# 07-AUDIO_MAIN.net
KiCad netlist of a schematic drawn in Altium Designer
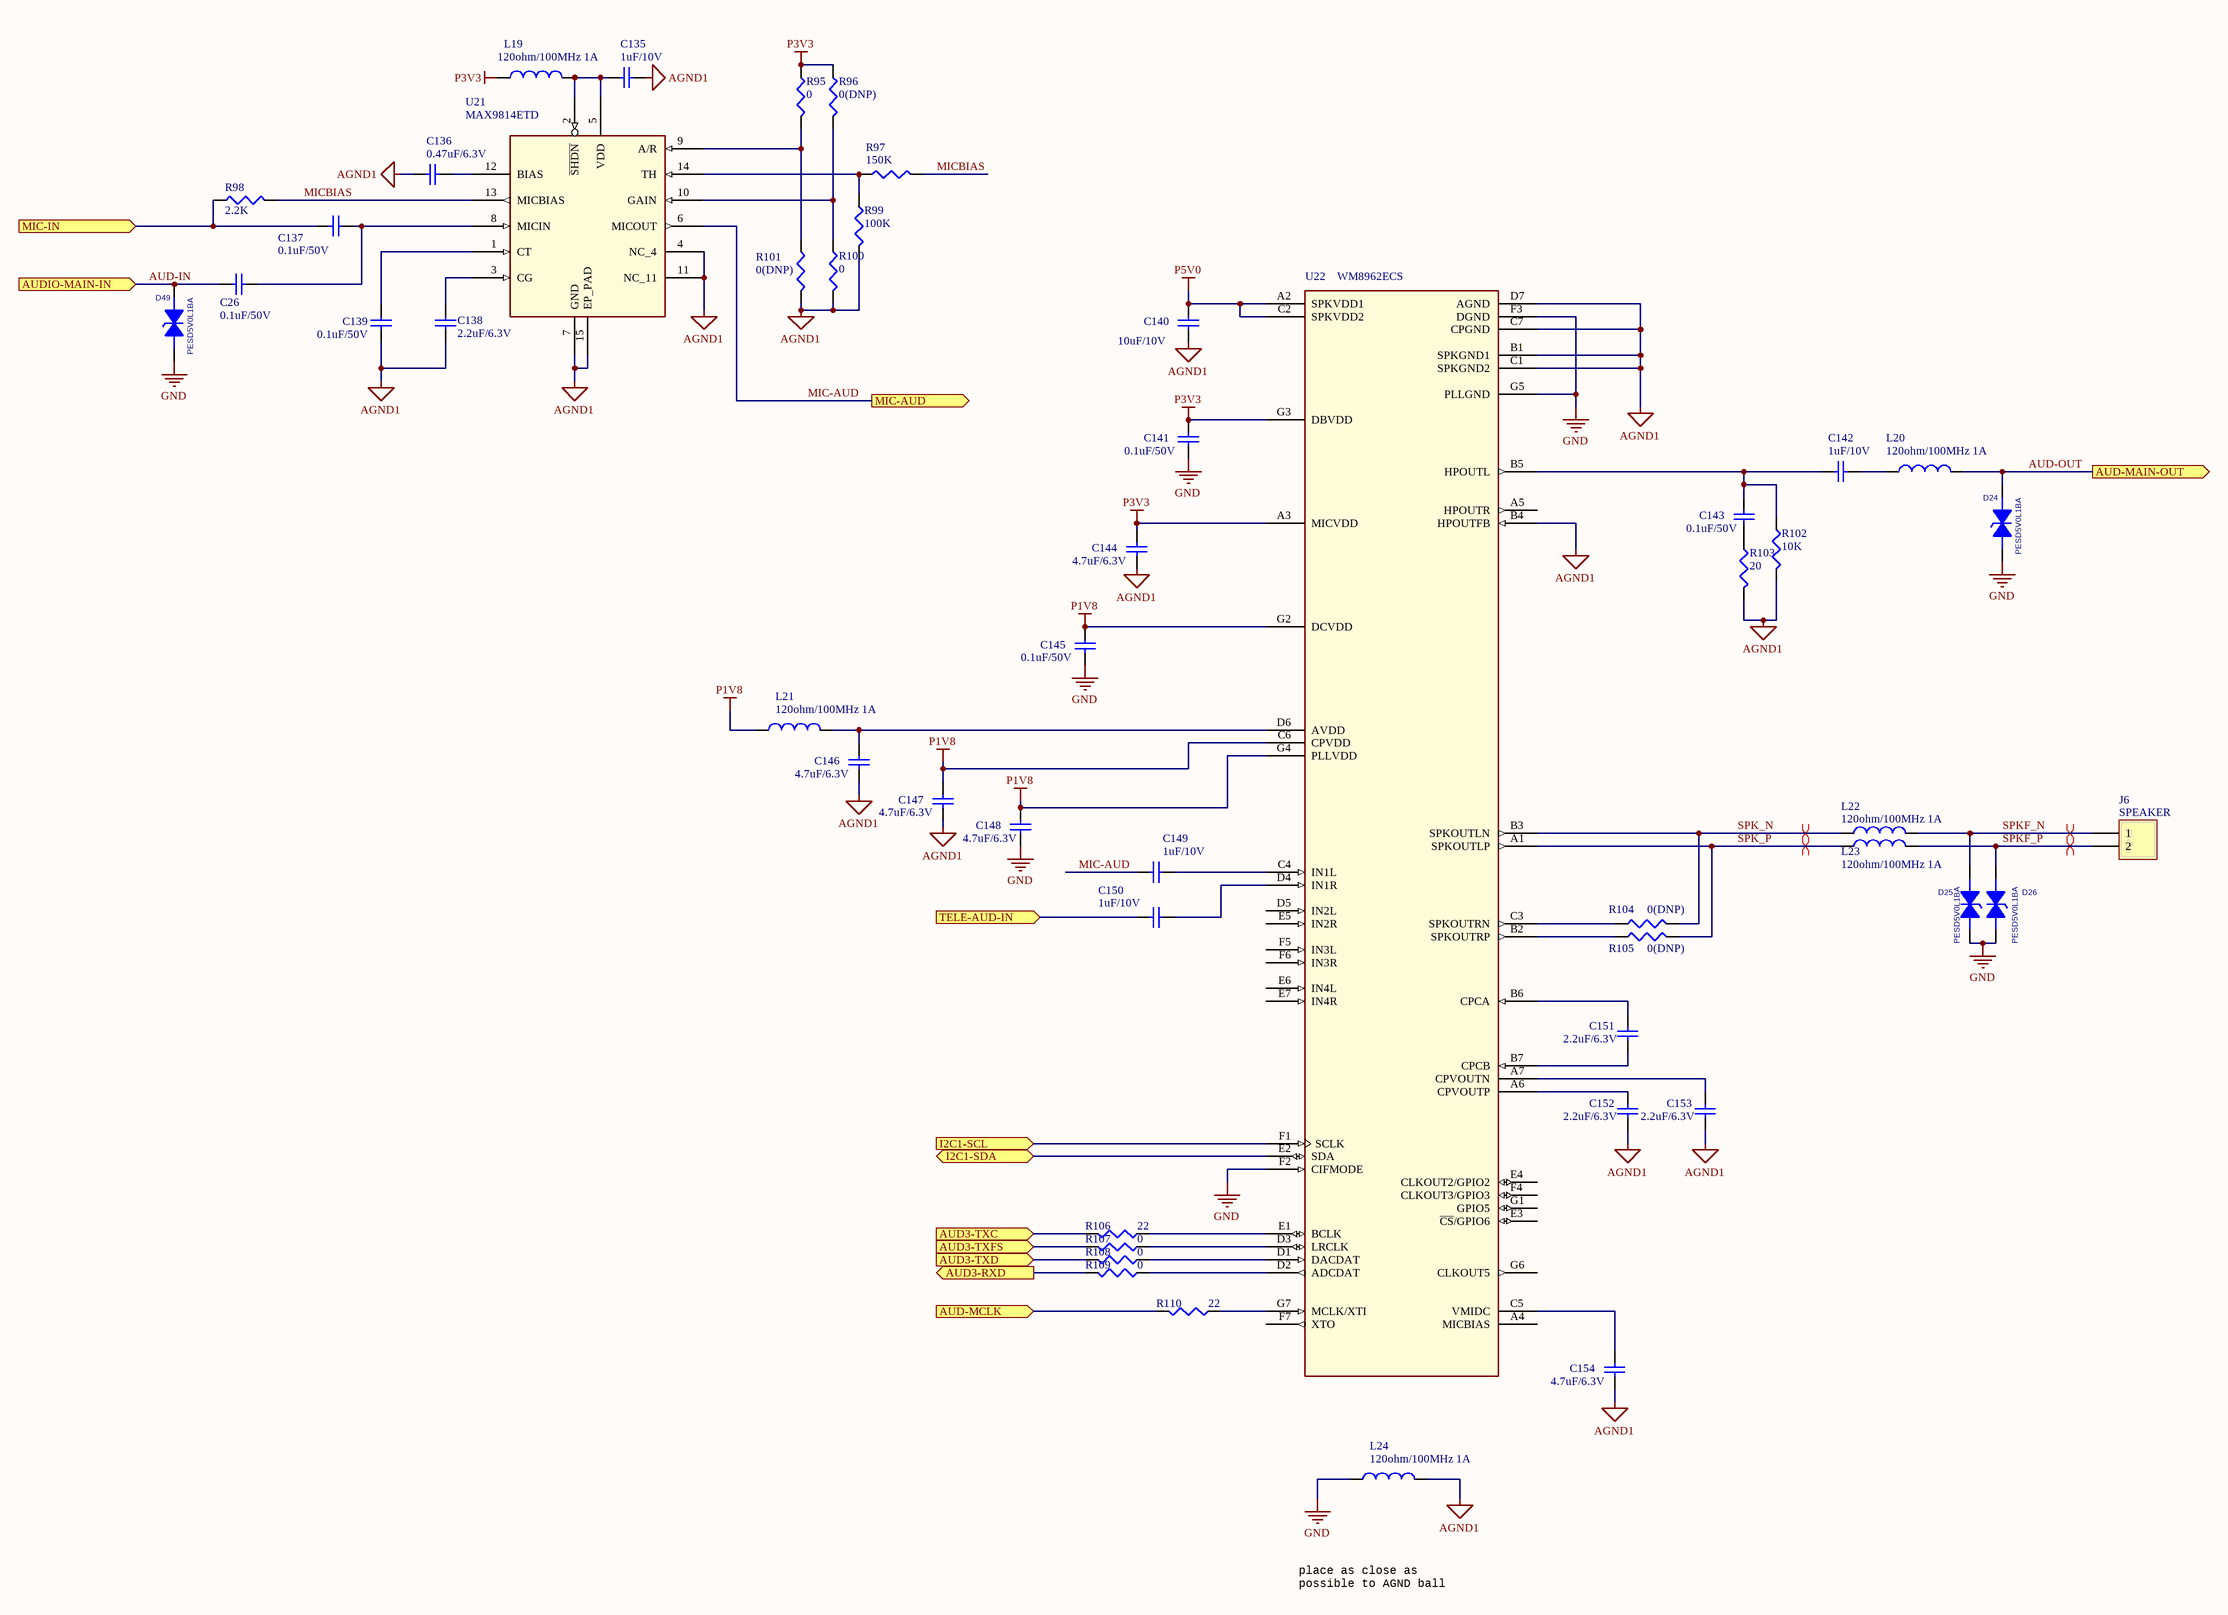
[diagram p0: 07-AUDIO_MAIN.SchDoc]

(export (version "E")
  (design (tool "Eeschema 10.0.6"))
  (components
    (comp (ref "C26")
      (value "0.1uF/50V")
      (footprint "0402")
      (description "Capacitor")
      (fields (field (name "PUBLISHER") "Altium Limited"))
      (libsource (lib "Miscellaneous Devices") (part "Cap"))
    )
    (comp (ref "C135")
      (value "1uF/10V")
      (footprint "0402")
      (description "Capacitor")
      (fields (field (name "PUBLISHER") "Altium Limited"))
      (libsource (lib "Miscellaneous Devices") (part "Cap"))
    )
    (comp (ref "C136")
      (value "0.47uF/6.3V")
      (footprint "0402")
      (description "Capacitor")
      (fields (field (name "PUBLISHER") "Altium Limited"))
      (libsource (lib "Miscellaneous Devices") (part "Cap"))
    )
    (comp (ref "C137")
      (value "0.1uF/50V")
      (footprint "0402")
      (description "Capacitor")
      (fields (field (name "PUBLISHER") "Altium Limited"))
      (libsource (lib "Miscellaneous Devices") (part "Cap"))
    )
    (comp (ref "C138")
      (value "2.2uF/6.3V")
      (footprint "0402")
      (description "Capacitor")
      (fields (field (name "PUBLISHER") "Altium Limited"))
      (libsource (lib "Miscellaneous Devices") (part "Cap"))
    )
    (comp (ref "C139")
      (value "0.1uF/50V")
      (footprint "0402")
      (description "Capacitor")
      (fields (field (name "PUBLISHER") "Altium Limited"))
      (libsource (lib "Miscellaneous Devices") (part "Cap"))
    )
    (comp (ref "C140")
      (value "10uF/10V")
      (footprint "0805")
      (description "Capacitor")
      (fields (field (name "PUBLISHER") "Altium Limited"))
      (libsource (lib "Miscellaneous Devices") (part "Cap"))
    )
    (comp (ref "C141")
      (value "0.1uF/50V")
      (footprint "0402")
      (description "Capacitor")
      (fields (field (name "PUBLISHER") "Altium Limited"))
      (libsource (lib "Miscellaneous Devices") (part "Cap"))
    )
    (comp (ref "C142")
      (value "1uF/10V")
      (footprint "0402")
      (description "Capacitor")
      (fields (field (name "PUBLISHER") "Altium Limited"))
      (libsource (lib "Miscellaneous Devices") (part "Cap"))
    )
    (comp (ref "C143")
      (value "0.1uF/50V")
      (footprint "0402")
      (description "Capacitor")
      (fields (field (name "PUBLISHER") "Altium Limited"))
      (libsource (lib "Miscellaneous Devices") (part "Cap"))
    )
    (comp (ref "C144")
      (value "4.7uF/6.3V")
      (footprint "0603")
      (description "Capacitor")
      (fields (field (name "PUBLISHER") "Altium Limited"))
      (libsource (lib "Miscellaneous Devices") (part "Cap"))
    )
    (comp (ref "C145")
      (value "0.1uF/50V")
      (footprint "0402")
      (description "Capacitor")
      (fields (field (name "PUBLISHER") "Altium Limited"))
      (libsource (lib "Miscellaneous Devices") (part "Cap"))
    )
    (comp (ref "C146")
      (value "4.7uF/6.3V")
      (footprint "0603")
      (description "Capacitor")
      (fields (field (name "PUBLISHER") "Altium Limited"))
      (libsource (lib "Miscellaneous Devices") (part "Cap"))
    )
    (comp (ref "C147")
      (value "4.7uF/6.3V")
      (footprint "0603")
      (description "Capacitor")
      (fields (field (name "PUBLISHER") "Altium Limited"))
      (libsource (lib "Miscellaneous Devices") (part "Cap"))
    )
    (comp (ref "C148")
      (value "4.7uF/6.3V")
      (footprint "0603")
      (description "Capacitor")
      (fields (field (name "PUBLISHER") "Altium Limited"))
      (libsource (lib "Miscellaneous Devices") (part "Cap"))
    )
    (comp (ref "C149")
      (value "1uF/10V")
      (footprint "0402")
      (description "Capacitor")
      (fields (field (name "PUBLISHER") "Altium Limited"))
      (libsource (lib "Miscellaneous Devices") (part "Cap"))
    )
    (comp (ref "C150")
      (value "1uF/10V")
      (footprint "0402")
      (description "Capacitor")
      (fields (field (name "PUBLISHER") "Altium Limited"))
      (libsource (lib "Miscellaneous Devices") (part "Cap"))
    )
    (comp (ref "C151")
      (value "2.2uF/6.3V")
      (footprint "0402")
      (description "Capacitor")
      (fields (field (name "PUBLISHER") "Altium Limited"))
      (libsource (lib "Miscellaneous Devices") (part "Cap"))
    )
    (comp (ref "C152")
      (value "2.2uF/6.3V")
      (footprint "0402")
      (description "Capacitor")
      (fields (field (name "PUBLISHER") "Altium Limited"))
      (libsource (lib "Miscellaneous Devices") (part "Cap"))
    )
    (comp (ref "C153")
      (value "2.2uF/6.3V")
      (footprint "0402")
      (description "Capacitor")
      (fields (field (name "PUBLISHER") "Altium Limited"))
      (libsource (lib "Miscellaneous Devices") (part "Cap"))
    )
    (comp (ref "C154")
      (value "4.7uF/6.3V")
      (footprint "0603")
      (description "Capacitor")
      (fields (field (name "PUBLISHER") "Altium Limited"))
      (libsource (lib "Miscellaneous Devices") (part "Cap"))
    )
    (comp (ref "D24") (value "PESD5V0L1BA") (libsource (lib "*") (part "PESD")))
    (comp (ref "D25") (value "PESD5V0L1BA") (libsource (lib "*") (part "PESD")))
    (comp (ref "D26") (value "PESD5V0L1BA") (libsource (lib "*") (part "PESD")))
    (comp (ref "D49") (value "PESD5V0L1BA") (libsource (lib "*") (part "PESD")))
    (comp (ref "J6")
      (value "SPEAKER")
      (footprint "1250WV-S-2P")
      (description "Header, 2-Pin")
      (fields (field (name "PUBLISHER") "Altium Limited"))
      (libsource (lib "Miscellaneous Connectors") (part "Header 2"))
    )
    (comp (ref "L19")
      (value "120ohm/100MHz 1A")
      (footprint "0603")
      (description "Inductor")
      (fields (field (name "PUBLISHER") "Altium Limited"))
      (libsource (lib "") (part "Inductor_1"))
    )
    (comp (ref "L20")
      (value "120ohm/100MHz 1A")
      (footprint "0603")
      (description "Inductor")
      (fields (field (name "PUBLISHER") "Altium Limited"))
      (libsource (lib "") (part "Inductor_1"))
    )
    (comp (ref "L21")
      (value "120ohm/100MHz 1A")
      (footprint "0603")
      (description "Inductor")
      (fields (field (name "PUBLISHER") "Altium Limited"))
      (libsource (lib "") (part "Inductor_1"))
    )
    (comp (ref "L22")
      (value "120ohm/100MHz 1A")
      (footprint "0603")
      (description "Inductor")
      (fields (field (name "PUBLISHER") "Altium Limited"))
      (libsource (lib "Miscellaneous Devices") (part "Inductor"))
    )
    (comp (ref "L23")
      (value "120ohm/100MHz 1A")
      (footprint "0603")
      (description "Inductor")
      (fields (field (name "PUBLISHER") "Altium Limited"))
      (libsource (lib "Miscellaneous Devices") (part "Inductor"))
    )
    (comp (ref "L24")
      (value "120ohm/100MHz 1A")
      (footprint "0603")
      (description "Inductor")
      (fields (field (name "PUBLISHER") "Altium Limited"))
      (libsource (lib "") (part "Inductor_1"))
    )
    (comp (ref "R95") (value "0") (footprint "0402") (libsource (lib "*") (part "CR16-1003FM")))
    (comp (ref "R96") (value "0(DNP)") (footprint "0402") (libsource (lib "*") (part "CR16-1003FM")))
    (comp (ref "R97") (value "150K") (footprint "0402") (libsource (lib "*") (part "CR16-1003FM")))
    (comp (ref "R98") (value "2.2K") (footprint "0402") (libsource (lib "*") (part "CR16-1003FM")))
    (comp (ref "R99") (value "100K") (footprint "0402") (libsource (lib "*") (part "CR16-1003FM")))
    (comp (ref "R100") (value "0") (footprint "0402") (libsource (lib "*") (part "CR16-1003FM")))
    (comp (ref "R101") (value "0(DNP)") (footprint "0402") (libsource (lib "*") (part "CR16-1003FM")))
    (comp (ref "R102") (value "10K") (footprint "0402") (libsource (lib "*") (part "CR16-1003FM")))
    (comp (ref "R103") (value "20") (footprint "0402") (libsource (lib "*") (part "CR16-1003FM")))
    (comp (ref "R104") (value "0(DNP)") (footprint "0402") (libsource (lib "*") (part "CR16-1003FM")))
    (comp (ref "R105") (value "0(DNP)") (footprint "0402") (libsource (lib "*") (part "CR16-1003FM")))
    (comp (ref "R106") (value "22") (footprint "0402") (libsource (lib "*") (part "CR16-1003FM")))
    (comp (ref "R107") (value "0") (footprint "0402") (libsource (lib "*") (part "CR16-1003FM")))
    (comp (ref "R108") (value "0") (footprint "0402") (libsource (lib "*") (part "CR16-1003FM")))
    (comp (ref "R109") (value "0") (footprint "0402") (libsource (lib "*") (part "CR16-1003FM")))
    (comp (ref "R110") (value "22") (footprint "0402") (libsource (lib "*") (part "CR16-1003FM")))
    (comp (ref "U21")
      (value "MAX9814ETD")
      (footprint "TDFN14")
      (description "IC LIN AGC AMP 2.7-5.5V TDFN14")
      (libsource (lib "*") (part "MAX9814_TDFN14"))
    )
    (comp (ref "U22")
      (value "WM8962ECS")
      (footprint "BGA49")
      (description "IC AUDIO CODEC 24BIT DAC 2 CH ADC 1.8V BGA49")
      (libsource (lib "*") (part "WM8962_BGA_49P_CUST"))
    )
  )
  (nets
    (net (code "1") (name "/AUD-IN") (class "Default")
      (node (ref "C26") (pin "1") (pinfunction "1_1") (pintype "passive"))
      (node (ref "D49") (pin "2") (pinfunction "2_2") (pintype "passive"))
    )
    (net (code "2") (name "/AUD-MCLK") (class "Default")
      (node (ref "R110") (pin "2") (pinfunction "2_2") (pintype "passive"))
    )
    (net (code "3") (name "/AUD-OUT") (class "Default")
      (node (ref "D24") (pin "2") (pinfunction "2_2") (pintype "passive"))
      (node (ref "L20") (pin "2") (pinfunction "2_2") (pintype "passive"))
    )
    (net (code "4") (name "/AUD3-RXD") (class "Default")
      (node (ref "R109") (pin "2") (pinfunction "2_2") (pintype "passive"))
    )
    (net (code "5") (name "/AUD3-TXC") (class "Default")
      (node (ref "R106") (pin "2") (pinfunction "2_2") (pintype "passive"))
    )
    (net (code "6") (name "/AUD3-TXD") (class "Default")
      (node (ref "R108") (pin "2") (pinfunction "2_2") (pintype "passive"))
    )
    (net (code "7") (name "/AUD3-TXFS") (class "Default")
      (node (ref "R107") (pin "2") (pinfunction "2_2") (pintype "passive"))
    )
    (net (code "8") (name "/I2C1-SCL") (class "Default")
      (node (ref "U22") (pin "F1") (pinfunction "SCLK_F1") (pintype "input"))
    )
    (net (code "9") (name "/I2C1-SDA") (class "Default")
      (node (ref "U22") (pin "E2") (pinfunction "SDA_E2") (pintype "bidirectional"))
    )
    (net (code "10") (name "/MIC-AUD") (class "Default")
      (node (ref "C149") (pin "2") (pinfunction "2_2") (pintype "passive"))
      (node (ref "U21") (pin "6") (pinfunction "MICOUT_6") (pintype "output"))
    )
    (net (code "11") (name "/MIC-IN") (class "Default")
      (node (ref "C137") (pin "2") (pinfunction "2_2") (pintype "passive"))
      (node (ref "R98") (pin "1") (pinfunction "1_1") (pintype "passive"))
    )
    (net (code "12") (name "/MICBIAS") (class "Default")
      (node (ref "R97") (pin "2") (pinfunction "2_2") (pintype "passive"))
      (node (ref "R98") (pin "2") (pinfunction "2_2") (pintype "passive"))
      (node (ref "U21") (pin "13") (pinfunction "MICBIAS_13") (pintype "output"))
    )
    (net (code "13") (name "/SPKF_N") (class "Default")
      (node (ref "D25") (pin "2") (pinfunction "2_2") (pintype "passive"))
      (node (ref "J6") (pin "1") (pinfunction "1_1") (pintype "passive"))
      (node (ref "L22") (pin "1") (pinfunction "1_1") (pintype "passive"))
    )
    (net (code "14") (name "/SPKF_P") (class "Default")
      (node (ref "D26") (pin "2") (pinfunction "2_2") (pintype "passive"))
      (node (ref "J6") (pin "2") (pinfunction "2_2") (pintype "passive"))
      (node (ref "L23") (pin "1") (pinfunction "1_1") (pintype "passive"))
    )
    (net (code "15") (name "/SPK_N") (class "Default")
      (node (ref "L22") (pin "2") (pinfunction "2_2") (pintype "passive"))
      (node (ref "R104") (pin "2") (pinfunction "2_2") (pintype "passive"))
      (node (ref "U22") (pin "B3") (pinfunction "SPKOUTLN_B3") (pintype "output"))
    )
    (net (code "16") (name "/SPK_P") (class "Default")
      (node (ref "L23") (pin "2") (pinfunction "2_2") (pintype "passive"))
      (node (ref "R105") (pin "2") (pinfunction "2_2") (pintype "passive"))
      (node (ref "U22") (pin "A1") (pinfunction "SPKOUTLP_A1") (pintype "output"))
    )
    (net (code "17") (name "/TELE-AUD-IN") (class "Default")
      (node (ref "C150") (pin "2") (pinfunction "2_2") (pintype "passive"))
    )
    (net (code "18") (name "AGND1") (class "Default")
      (node (ref "C135") (pin "1") (pinfunction "1_1") (pintype "passive"))
      (node (ref "C136") (pin "2") (pinfunction "2_2") (pintype "passive"))
      (node (ref "C138") (pin "2") (pinfunction "2_2") (pintype "passive"))
      (node (ref "C139") (pin "2") (pinfunction "2_2") (pintype "passive"))
      (node (ref "C140") (pin "1") (pinfunction "1_1") (pintype "passive"))
      (node (ref "C144") (pin "1") (pinfunction "1_1") (pintype "passive"))
      (node (ref "C146") (pin "1") (pinfunction "1_1") (pintype "passive"))
      (node (ref "C147") (pin "1") (pinfunction "1_1") (pintype "passive"))
      (node (ref "C152") (pin "1") (pinfunction "1_1") (pintype "passive"))
      (node (ref "C153") (pin "1") (pinfunction "1_1") (pintype "passive"))
      (node (ref "C154") (pin "1") (pinfunction "1_1") (pintype "passive"))
      (node (ref "L24") (pin "2") (pinfunction "2_2") (pintype "passive"))
      (node (ref "R100") (pin "2") (pinfunction "2_2") (pintype "passive"))
      (node (ref "R101") (pin "2") (pinfunction "2_2") (pintype "passive"))
      (node (ref "R102") (pin "2") (pinfunction "2_2") (pintype "passive"))
      (node (ref "R103") (pin "2") (pinfunction "2_2") (pintype "passive"))
      (node (ref "R99") (pin "2") (pinfunction "2_2") (pintype "passive"))
      (node (ref "U21") (pin "11") (pinfunction "NC_11_11") (pintype "passive"))
      (node (ref "U21") (pin "15") (pinfunction "EP_PAD_15") (pintype "power_in"))
      (node (ref "U21") (pin "4") (pinfunction "NC_4_4") (pintype "passive"))
      (node (ref "U21") (pin "7") (pinfunction "GND_7") (pintype "power_in"))
      (node (ref "U22") (pin "B1") (pinfunction "SPKGND1_B1") (pintype "power_in"))
      (node (ref "U22") (pin "B4") (pinfunction "HPOUTFB_B4") (pintype "input"))
      (node (ref "U22") (pin "C1") (pinfunction "SPKGND2_C1") (pintype "power_in"))
      (node (ref "U22") (pin "C7") (pinfunction "CPGND_C7") (pintype "power_in"))
      (node (ref "U22") (pin "D7") (pinfunction "AGND_D7") (pintype "power_in"))
    )
    (net (code "19") (name "GND") (class "Default")
      (node (ref "C141") (pin "1") (pinfunction "1_1") (pintype "passive"))
      (node (ref "C145") (pin "1") (pinfunction "1_1") (pintype "passive"))
      (node (ref "C148") (pin "1") (pinfunction "1_1") (pintype "passive"))
      (node (ref "D24") (pin "1") (pinfunction "1_1") (pintype "passive"))
      (node (ref "D25") (pin "1") (pinfunction "1_1") (pintype "passive"))
      (node (ref "D26") (pin "1") (pinfunction "1_1") (pintype "passive"))
      (node (ref "D49") (pin "1") (pinfunction "1_1") (pintype "passive"))
      (node (ref "L24") (pin "1") (pinfunction "1_1") (pintype "passive"))
      (node (ref "U22") (pin "F2") (pinfunction "CIFMODE_F2") (pintype "input"))
      (node (ref "U22") (pin "F3") (pinfunction "DGND_F3") (pintype "power_in"))
      (node (ref "U22") (pin "G5") (pinfunction "PLLGND_G5") (pintype "power_in"))
    )
    (net (code "20") (name "Net-(C142-Pad1)") (class "Default")
      (node (ref "C142") (pin "1") (pinfunction "1_1") (pintype "passive"))
      (node (ref "L20") (pin "1") (pinfunction "1_1") (pintype "passive"))
    )
    (net (code "21") (name "Net-(C143-Pad1)") (class "Default")
      (node (ref "C143") (pin "1") (pinfunction "1_1") (pintype "passive"))
      (node (ref "R103") (pin "1") (pinfunction "1_1") (pintype "passive"))
    )
    (net (code "22") (name "Net-(U21-A{slash}R)") (class "Default")
      (node (ref "R101") (pin "1") (pinfunction "1_1") (pintype "passive"))
      (node (ref "R95") (pin "2") (pinfunction "2_2") (pintype "passive"))
      (node (ref "U21") (pin "9") (pinfunction "A/R_9") (pintype "input"))
    )
    (net (code "23") (name "Net-(U21-BIAS)") (class "Default")
      (node (ref "C136") (pin "1") (pinfunction "1_1") (pintype "passive"))
      (node (ref "U21") (pin "12") (pinfunction "BIAS_12") (pintype "power_in"))
    )
    (net (code "24") (name "Net-(U21-CG)") (class "Default")
      (node (ref "C138") (pin "1") (pinfunction "1_1") (pintype "passive"))
      (node (ref "U21") (pin "3") (pinfunction "CG_3") (pintype "input"))
    )
    (net (code "25") (name "Net-(U21-CT)") (class "Default")
      (node (ref "C139") (pin "1") (pinfunction "1_1") (pintype "passive"))
      (node (ref "U21") (pin "1") (pinfunction "CT_1") (pintype "input"))
    )
    (net (code "26") (name "Net-(U21-GAIN)") (class "Default")
      (node (ref "R100") (pin "1") (pinfunction "1_1") (pintype "passive"))
      (node (ref "R96") (pin "2") (pinfunction "2_2") (pintype "passive"))
      (node (ref "U21") (pin "10") (pinfunction "GAIN_10") (pintype "input"))
    )
    (net (code "27") (name "Net-(U21-MICIN)") (class "Default")
      (node (ref "C137") (pin "1") (pinfunction "1_1") (pintype "passive"))
      (node (ref "C26") (pin "2") (pinfunction "2_2") (pintype "passive"))
      (node (ref "U21") (pin "8") (pinfunction "MICIN_8") (pintype "input"))
    )
    (net (code "28") (name "Net-(U21-TH)") (class "Default")
      (node (ref "R97") (pin "1") (pinfunction "1_1") (pintype "passive"))
      (node (ref "R99") (pin "1") (pinfunction "1_1") (pintype "passive"))
      (node (ref "U21") (pin "14") (pinfunction "TH_14") (pintype "input"))
    )
    (net (code "29") (name "Net-(U21-VDD)") (class "Default")
      (node (ref "C135") (pin "2") (pinfunction "2_2") (pintype "passive"))
      (node (ref "L19") (pin "2") (pinfunction "2_2") (pintype "passive"))
      (node (ref "U21") (pin "2") (pinfunction "~{SHDN}_2") (pintype "input"))
      (node (ref "U21") (pin "5") (pinfunction "VDD_5") (pintype "power_in"))
    )
    (net (code "30") (name "Net-(U22-ADCDAT)") (class "Default")
      (node (ref "R109") (pin "1") (pinfunction "1_1") (pintype "passive"))
      (node (ref "U22") (pin "D2") (pinfunction "ADCDAT_D2") (pintype "output"))
    )
    (net (code "31") (name "Net-(U22-AVDD)") (class "Default")
      (node (ref "C146") (pin "2") (pinfunction "2_2") (pintype "passive"))
      (node (ref "L21") (pin "2") (pinfunction "2_2") (pintype "passive"))
      (node (ref "U22") (pin "D6") (pinfunction "AVDD_D6") (pintype "power_in"))
    )
    (net (code "32") (name "Net-(U22-BCLK)") (class "Default")
      (node (ref "R106") (pin "1") (pinfunction "1_1") (pintype "passive"))
      (node (ref "U22") (pin "E1") (pinfunction "BCLK_E1") (pintype "bidirectional"))
    )
    (net (code "33") (name "Net-(U22-CPCA)") (class "Default")
      (node (ref "C151") (pin "2") (pinfunction "2_2") (pintype "passive"))
      (node (ref "U22") (pin "B6") (pinfunction "CPCA_B6") (pintype "input"))
    )
    (net (code "34") (name "Net-(U22-CPCB)") (class "Default")
      (node (ref "C151") (pin "1") (pinfunction "1_1") (pintype "passive"))
      (node (ref "U22") (pin "B7") (pinfunction "CPCB_B7") (pintype "input"))
    )
    (net (code "35") (name "Net-(U22-CPVOUTN)") (class "Default")
      (node (ref "C153") (pin "2") (pinfunction "2_2") (pintype "passive"))
      (node (ref "U22") (pin "A7") (pinfunction "CPVOUTN_A7") (pintype "power_in"))
    )
    (net (code "36") (name "Net-(U22-CPVOUTP)") (class "Default")
      (node (ref "C152") (pin "2") (pinfunction "2_2") (pintype "passive"))
      (node (ref "U22") (pin "A6") (pinfunction "CPVOUTP_A6") (pintype "power_in"))
    )
    (net (code "37") (name "Net-(U22-DACDAT)") (class "Default")
      (node (ref "R108") (pin "1") (pinfunction "1_1") (pintype "passive"))
      (node (ref "U22") (pin "D1") (pinfunction "DACDAT_D1") (pintype "input"))
    )
    (net (code "38") (name "Net-(U22-HPOUTL)") (class "Default")
      (node (ref "C142") (pin "2") (pinfunction "2_2") (pintype "passive"))
      (node (ref "C143") (pin "2") (pinfunction "2_2") (pintype "passive"))
      (node (ref "R102") (pin "1") (pinfunction "1_1") (pintype "passive"))
      (node (ref "U22") (pin "B5") (pinfunction "HPOUTL_B5") (pintype "output"))
    )
    (net (code "39") (name "Net-(U22-IN1L)") (class "Default")
      (node (ref "C149") (pin "1") (pinfunction "1_1") (pintype "passive"))
      (node (ref "U22") (pin "C4") (pinfunction "IN1L_C4") (pintype "input"))
    )
    (net (code "40") (name "Net-(U22-IN1R)") (class "Default")
      (node (ref "C150") (pin "1") (pinfunction "1_1") (pintype "passive"))
      (node (ref "U22") (pin "D4") (pinfunction "IN1R_D4") (pintype "input"))
    )
    (net (code "41") (name "Net-(U22-LRCLK)") (class "Default")
      (node (ref "R107") (pin "1") (pinfunction "1_1") (pintype "passive"))
      (node (ref "U22") (pin "D3") (pinfunction "LRCLK_D3") (pintype "bidirectional"))
    )
    (net (code "42") (name "Net-(U22-MCLK{slash}XTI)") (class "Default")
      (node (ref "R110") (pin "1") (pinfunction "1_1") (pintype "passive"))
      (node (ref "U22") (pin "G7") (pinfunction "MCLK/XTI_G7") (pintype "input"))
    )
    (net (code "43") (name "Net-(U22-SPKOUTRN)") (class "Default")
      (node (ref "R104") (pin "1") (pinfunction "1_1") (pintype "passive"))
      (node (ref "U22") (pin "C3") (pinfunction "SPKOUTRN_C3") (pintype "output"))
    )
    (net (code "44") (name "Net-(U22-SPKOUTRP)") (class "Default")
      (node (ref "R105") (pin "1") (pinfunction "1_1") (pintype "passive"))
      (node (ref "U22") (pin "B2") (pinfunction "SPKOUTRP_B2") (pintype "output"))
    )
    (net (code "45") (name "Net-(U22-VMIDC)") (class "Default")
      (node (ref "C154") (pin "2") (pinfunction "2_2") (pintype "passive"))
      (node (ref "U22") (pin "C5") (pinfunction "VMIDC_C5") (pintype "power_in"))
    )
    (net (code "46") (name "P1V8") (class "Default")
      (node (ref "C145") (pin "2") (pinfunction "2_2") (pintype "passive"))
      (node (ref "C147") (pin "2") (pinfunction "2_2") (pintype "passive"))
      (node (ref "C148") (pin "2") (pinfunction "2_2") (pintype "passive"))
      (node (ref "L21") (pin "1") (pinfunction "1_1") (pintype "passive"))
      (node (ref "U22") (pin "C6") (pinfunction "CPVDD_C6") (pintype "power_in"))
      (node (ref "U22") (pin "G2") (pinfunction "DCVDD_G2") (pintype "power_in"))
      (node (ref "U22") (pin "G4") (pinfunction "PLLVDD_G4") (pintype "power_in"))
    )
    (net (code "47") (name "P3V3") (class "Default")
      (node (ref "C141") (pin "2") (pinfunction "2_2") (pintype "passive"))
      (node (ref "C144") (pin "2") (pinfunction "2_2") (pintype "passive"))
      (node (ref "L19") (pin "1") (pinfunction "1_1") (pintype "passive"))
      (node (ref "R95") (pin "1") (pinfunction "1_1") (pintype "passive"))
      (node (ref "R96") (pin "1") (pinfunction "1_1") (pintype "passive"))
      (node (ref "U22") (pin "A3") (pinfunction "MICVDD_A3") (pintype "power_in"))
      (node (ref "U22") (pin "G3") (pinfunction "DBVDD_G3") (pintype "power_in"))
    )
    (net (code "48") (name "P5V0") (class "Default")
      (node (ref "C140") (pin "2") (pinfunction "2_2") (pintype "passive"))
      (node (ref "U22") (pin "A2") (pinfunction "SPKVDD1_A2") (pintype "power_in"))
      (node (ref "U22") (pin "C2") (pinfunction "SPKVDD2_C2") (pintype "power_in"))
    )
    (net (code "49") (name "unconnected-(U22-CLKOUT2{slash}GPIO2-PadE4)") (class "Default")
      (node (ref "U22") (pin "E4") (pinfunction "CLKOUT2/GPIO2_E4") (pintype "bidirectional"))
    )
    (net (code "50") (name "unconnected-(U22-CLKOUT3{slash}GPIO3-PadF4)") (class "Default")
      (node (ref "U22") (pin "F4") (pinfunction "CLKOUT3/GPIO3_F4") (pintype "bidirectional"))
    )
    (net (code "51") (name "unconnected-(U22-CLKOUT5-PadG6)") (class "Default")
      (node (ref "U22") (pin "G6") (pinfunction "CLKOUT5_G6") (pintype "output"))
    )
    (net (code "52") (name "unconnected-(U22-GPIO5-PadG1)") (class "Default")
      (node (ref "U22") (pin "G1") (pinfunction "GPIO5_G1") (pintype "bidirectional"))
    )
    (net (code "53") (name "unconnected-(U22-HPOUTR-PadA5)") (class "Default")
      (node (ref "U22") (pin "A5") (pinfunction "HPOUTR_A5") (pintype "output"))
    )
    (net (code "54") (name "unconnected-(U22-IN2L-PadD5)") (class "Default")
      (node (ref "U22") (pin "D5") (pinfunction "IN2L_D5") (pintype "input"))
    )
    (net (code "55") (name "unconnected-(U22-IN2R-PadE5)") (class "Default")
      (node (ref "U22") (pin "E5") (pinfunction "IN2R_E5") (pintype "input"))
    )
    (net (code "56") (name "unconnected-(U22-IN3L-PadF5)") (class "Default")
      (node (ref "U22") (pin "F5") (pinfunction "IN3L_F5") (pintype "input"))
    )
    (net (code "57") (name "unconnected-(U22-IN3R-PadF6)") (class "Default")
      (node (ref "U22") (pin "F6") (pinfunction "IN3R_F6") (pintype "input"))
    )
    (net (code "58") (name "unconnected-(U22-IN4L-PadE6)") (class "Default")
      (node (ref "U22") (pin "E6") (pinfunction "IN4L_E6") (pintype "input"))
    )
    (net (code "59") (name "unconnected-(U22-IN4R-PadE7)") (class "Default")
      (node (ref "U22") (pin "E7") (pinfunction "IN4R_E7") (pintype "input"))
    )
    (net (code "60") (name "unconnected-(U22-MICBIAS-PadA4)") (class "Default")
      (node (ref "U22") (pin "A4") (pinfunction "MICBIAS_A4") (pintype "passive"))
    )
    (net (code "61") (name "unconnected-(U22-XTO-PadF7)") (class "Default")
      (node (ref "U22") (pin "F7") (pinfunction "XTO_F7") (pintype "output"))
    )
    (net (code "62") (name "unconnected-(U22-~{CS}{slash}GPIO6-PadE3)") (class "Default")
      (node (ref "U22") (pin "E3") (pinfunction "~{CS}/GPIO6_E3") (pintype "bidirectional"))
    )
  )
)
